# sheet2_buck_converter.net
KiCad netlist of a schematic drawn in Altium Designer
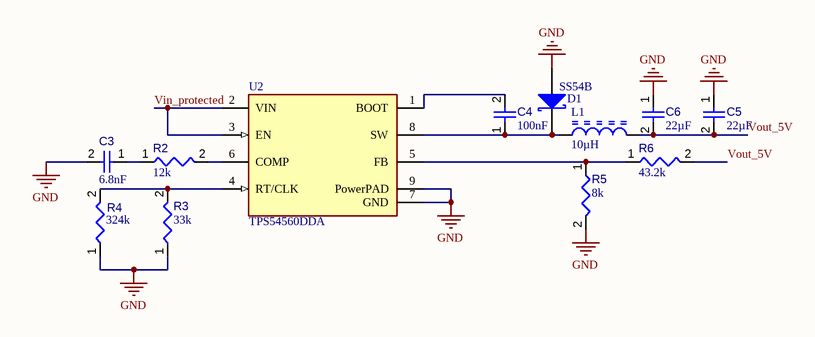
[diagram p0: sheet2_buck_converter.SchDoc]

(export (version "E")
  (design (tool "Eeschema 10.0.6"))
  (components
    (comp (ref "C3")
      (value "6.8nF")
      (footprint "CAPC1005X56X25NL10T15")
      (description "Chip Capacitor, 6.8 nF, +/- 10%, 16 V, 0402 (1005 Metric)")
      (fields (field (name "TOLERANCE") "10%") (field (name "Comment") "Capacitor 6.8 nF +/- 10% 16 V 0402"))
      (libsource (lib "University of Florida") (part "CAP-NP-2"))
    )
    (comp (ref "C4")
      (value "100nF")
      (footprint "CAPC1005X56X25LL10T15")
      (description "Chip Capacitor, 0.1 uF, +/- 5%, 16 V, 0402 (1005 Metric)")
      (fields (field (name "TOLERANCE") "5%") (field (name "Comment") "Capacitor 0.1 uF +/- 5% 16 V 0402"))
      (libsource (lib "University of Florida") (part "CAP-NP-2"))
    )
    (comp (ref "C5")
      (value "22µF")
      (footprint "CAPC0805(2012)145_L")
      (description "Chip Capacitor, 22µF +/-40%, 16V, 0805, Thickness 1.45 mm")
      (fields (field (name "TOLERANCE") "5%") (field (name "Comment") "Capacitor 22µF +/-40% 16V 0805"))
      (libsource (lib "University of Florida") (part "CAP-NP-2"))
    )
    (comp (ref "C6")
      (value "22µF")
      (footprint "CAPC0805(2012)145_L")
      (description "Chip Capacitor, 22µF +/-40%, 16V, 0805, Thickness 1.45 mm")
      (fields (field (name "TOLERANCE") "5%") (field (name "Comment") "Capacitor 22µF +/-40% 16V 0805"))
      (libsource (lib "University of Florida") (part "CAP-NP-2"))
    )
    (comp (ref "D1")
      (value "SS54B")
      (footprint "JCET-SMB-2_M")
      (description "Schottky Barrier Rectifier, 40 V, 5 A, -55 to 150 degC, 2-Pin SMD")
      (fields (field (name "MANUFACTURER") "JCET"))
      (libsource (lib "University of Florida") (part "DSKY-AK-2"))
    )
    (comp (ref "L1")
      (value "CM322522-100KL")
      (footprint "BOUR-CM322522_V")
      (description "Chip Inductor, 10 uH, +/- 10%, -40 to 125 degC, 1210 (3225 Metric), RoHS, Tape and Reel")
      (fields
        (field (name "INDUCTANCE") "10µH")
        (field (name "MANUFACTURER") "Bourns")
        (field (name "TOLERANCE") "10%")
      )
      (libsource (lib "University of Florida") (part "BOUR-IND-2A"))
    )
    (comp (ref "R2")
      (value "12k")
      (footprint "RESC0402(1005)_L")
      (description "12K 0.063W 1% 0402 (1005 Metric)  SMD")
      (fields (field (name "TOLERANCE") "1%") (field (name "POWER") "63mW"))
      (libsource (lib "University of Florida") (part "12KR2F"))
    )
    (comp (ref "R3")
      (value "33k")
      (footprint "RESC1005X40X25ML10T10")
      (description "Chip Resistor, 33 KOhm, +/- 5%, 0.063 W, -55 to 155 degC, 0402 (1005 Metric)")
      (fields (field (name "TOLERANCE") "5%") (field (name "POWER") "63mW"))
      (libsource (lib "University of Florida") (part "RES-2"))
    )
    (comp (ref "R4")
      (value "324k")
      (footprint "RESC0402(1005)_L")
      (description "324K 0.063W 1% 0402 (1005 Metric)  SMD")
      (fields (field (name "TOLERANCE") "1%") (field (name "POWER") "63mW"))
      (libsource (lib "University of Florida") (part "324KR2F"))
    )
    (comp (ref "R5")
      (value "8k")
      (footprint "RESC0402(1005)_L")
      (description "Chip Resistor, 5,6 kOhms, +/-5 %, 63 mW, -55 to 155 degC, 0402")
      (fields (field (name "POWER") "63mW") (field (name "TOLERANCE") "5%"))
      (libsource (lib "University of Florida") (part "RES-2"))
    )
    (comp (ref "R6")
      (value "43.2k")
      (footprint "RESC0402(1005)_L")
      (description "Chip Resistor, 43,2 kOhms, +/-1 %, 63 mW, -55 to 155 degC, 0402")
      (fields (field (name "TOLERANCE") "1%") (field (name "POWER") "63mW"))
      (libsource (lib "University of Florida") (part "RES-2"))
    )
    (comp (ref "U2")
      (value "TPS54560DDA")
      (footprint "FP-DDA0008E-MFG")
      (description "IC REG BCK SPLIT RAIL ADJ 8SOPWR")
      (fields
        (field (name "OCTOPART") "https://octopart.com/tps54560dda-texas+instruments-26977150")
        (field (name "MANUFACTURER") "Texas Instruments")
      )
      (libsource (lib "Altium Content Vault") (part "92fa32c5fb0b456cc3a934f0e7b6d8f"))
    )
  )
  (nets
    (net (code "1") (name "/Vin_protected") (class "Default")
      (node (ref "U2") (pin "2") (pinfunction "VIN_2") (pintype "power_in"))
      (node (ref "U2") (pin "3") (pinfunction "EN_3") (pintype "input"))
    )
    (net (code "2") (name "/Vout_5V") (class "Default")
      (node (ref "C5") (pin "2") (pinfunction "2_2") (pintype "passive"))
      (node (ref "C6") (pin "2") (pinfunction "2_2") (pintype "passive"))
      (node (ref "L1") (pin "2") (pinfunction "2_2") (pintype "passive"))
      (node (ref "R6") (pin "2") (pinfunction "2_2") (pintype "passive"))
    )
    (net (code "3") (name "GND") (class "Default")
      (node (ref "C3") (pin "2") (pinfunction "2_2") (pintype "passive"))
      (node (ref "C5") (pin "1") (pinfunction "1_1") (pintype "passive"))
      (node (ref "C6") (pin "1") (pinfunction "1_1") (pintype "passive"))
      (node (ref "D1") (pin "1") (pinfunction "A_1") (pintype "passive"))
      (node (ref "R3") (pin "1") (pinfunction "1_1") (pintype "passive"))
      (node (ref "R4") (pin "1") (pinfunction "1_1") (pintype "passive"))
      (node (ref "R5") (pin "2") (pinfunction "2_2") (pintype "passive"))
      (node (ref "U2") (pin "7") (pinfunction "GND_7") (pintype "power_in"))
      (node (ref "U2") (pin "9") (pinfunction "PowerPAD_9") (pintype "power_in"))
    )
    (net (code "4") (name "Net-(C3-Pad1)") (class "Default")
      (node (ref "C3") (pin "1") (pinfunction "1_1") (pintype "passive"))
      (node (ref "R2") (pin "1") (pinfunction "1_1") (pintype "passive"))
    )
    (net (code "5") (name "Net-(D1-K)") (class "Default")
      (node (ref "C4") (pin "1") (pinfunction "1_1") (pintype "passive"))
      (node (ref "D1") (pin "2") (pinfunction "K_2") (pintype "passive"))
      (node (ref "L1") (pin "1") (pinfunction "1_1") (pintype "passive"))
      (node (ref "U2") (pin "8") (pinfunction "SW_8") (pintype "passive"))
    )
    (net (code "6") (name "Net-(U2-BOOT)") (class "Default")
      (node (ref "C4") (pin "2") (pinfunction "2_2") (pintype "passive"))
      (node (ref "U2") (pin "1") (pinfunction "BOOT_1") (pintype "passive"))
    )
    (net (code "7") (name "Net-(U2-COMP)") (class "Default")
      (node (ref "R2") (pin "2") (pinfunction "2_2") (pintype "passive"))
      (node (ref "U2") (pin "6") (pinfunction "COMP_6") (pintype "passive"))
    )
    (net (code "8") (name "Net-(U2-FB)") (class "Default")
      (node (ref "R5") (pin "1") (pinfunction "1_1") (pintype "passive"))
      (node (ref "R6") (pin "1") (pinfunction "1_1") (pintype "passive"))
      (node (ref "U2") (pin "5") (pinfunction "FB_5") (pintype "passive"))
    )
    (net (code "9") (name "Net-(U2-RT{slash}CLK)") (class "Default")
      (node (ref "R3") (pin "2") (pinfunction "2_2") (pintype "passive"))
      (node (ref "R4") (pin "2") (pinfunction "2_2") (pintype "passive"))
      (node (ref "U2") (pin "4") (pinfunction "RT/CLK_4") (pintype "input"))
    )
  )
)
